# RemoteControl.net
KiCad netlist of a schematic drawn in EAGLE
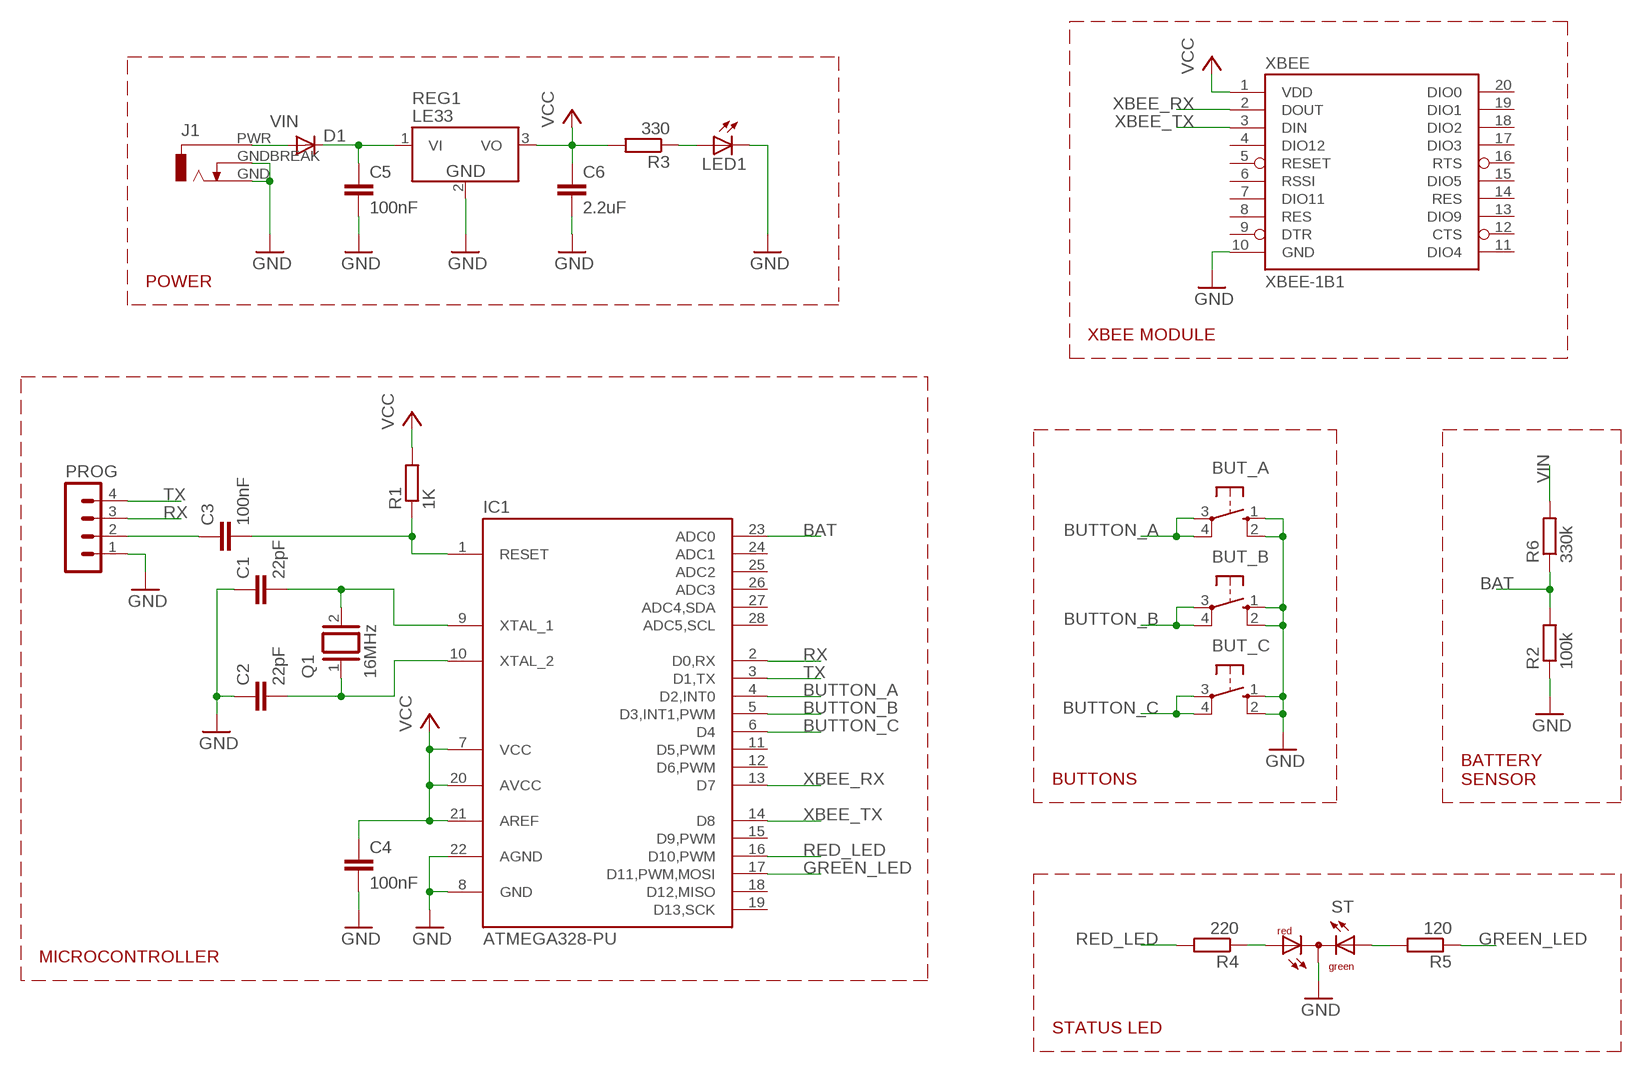
[diagram p0: schematic, sheet 1]

(export (version "E")
  (design (tool "Eeschema 10.0.6"))
  (components
    (comp (ref "BUT_A")
      (value "40-XX")
      (footprint "eagle-import:B3F-40XX")
      (fields (field (name "MF") "OMRON COMPONENTS USA") (field (name "MPN") "B3F-4000"))
      (libsource (lib "eagle-import") (part "40-XX"))
    )
    (comp (ref "BUT_B")
      (value "40-XX")
      (footprint "eagle-import:B3F-40XX")
      (fields (field (name "MF") "OMRON COMPONENTS USA") (field (name "MPN") "B3F-4000"))
      (libsource (lib "eagle-import") (part "40-XX"))
    )
    (comp (ref "BUT_C")
      (value "40-XX")
      (footprint "eagle-import:B3F-40XX")
      (fields (field (name "MF") "OMRON COMPONENTS USA") (field (name "MPN") "B3F-4000"))
      (libsource (lib "eagle-import") (part "40-XX"))
    )
    (comp (ref "C1")
      (value "22pF")
      (footprint "eagle-import:C050-024X044")
      (libsource (lib "eagle-import") (part "C-EU050-024X044"))
    )
    (comp (ref "C2")
      (value "22pF")
      (footprint "eagle-import:C050-024X044")
      (libsource (lib "eagle-import") (part "C-EU050-024X044"))
    )
    (comp (ref "C3")
      (value "100nF")
      (footprint "eagle-import:C050-025X075")
      (libsource (lib "eagle-import") (part "C-EU050-025X075"))
    )
    (comp (ref "C4")
      (value "100nF")
      (footprint "eagle-import:C050-025X075")
      (libsource (lib "eagle-import") (part "C-EU050-025X075"))
    )
    (comp (ref "C5")
      (value "100nF")
      (footprint "eagle-import:C050-025X075")
      (libsource (lib "eagle-import") (part "C-EU050-025X075"))
    )
    (comp (ref "C6")
      (value "2.2uF")
      (footprint "eagle-import:C050-035X075")
      (libsource (lib "eagle-import") (part "C-EU050-035X075"))
    )
    (comp (ref "D1")
      (value "1N4148DO35-7")
      (footprint "eagle-import:DO35-7")
      (libsource (lib "eagle-import") (part "1N4148DO35-7"))
    )
    (comp (ref "IC1")
      (value "ATMEGA328-PU")
      (footprint "eagle-import:DIL28-3")
      (libsource (lib "eagle-import") (part "ATMEGA328-PU"))
    )
    (comp (ref "J1")
      (value "DC_JACKPTH")
      (footprint "eagle-import:POWER_JACK_PTH")
      (libsource (lib "eagle-import") (part "DC_JACKPTH"))
    )
    (comp (ref "LED1")
      (value "LED3MM")
      (footprint "eagle-import:LED3MM")
      (libsource (lib "eagle-import") (part "LED3MM"))
    )
    (comp (ref "PROG")
      (value "MA04-1")
      (footprint "eagle-import:MA04-1")
      (libsource (lib "eagle-import") (part "MA04-1"))
    )
    (comp (ref "Q1")
      (value "16MHz")
      (footprint "eagle-import:QS")
      (libsource (lib "eagle-import") (part "XTAL/S"))
    )
    (comp (ref "R1")
      (value "1K")
      (footprint "eagle-import:0207_7")
      (libsource (lib "eagle-import") (part "R-EU_0207/7"))
    )
    (comp (ref "R2")
      (value "100k")
      (footprint "eagle-import:0207_7")
      (libsource (lib "eagle-import") (part "R-EU_0207/7"))
    )
    (comp (ref "R3")
      (value "330")
      (footprint "eagle-import:0207_7")
      (libsource (lib "eagle-import") (part "R-EU_0207/7"))
    )
    (comp (ref "R4")
      (value "220")
      (footprint "eagle-import:0207_7")
      (libsource (lib "eagle-import") (part "R-EU_0207/7"))
    )
    (comp (ref "R5")
      (value "120")
      (footprint "eagle-import:0207_7")
      (libsource (lib "eagle-import") (part "R-EU_0207/7"))
    )
    (comp (ref "R6")
      (value "330k")
      (footprint "eagle-import:0207_7")
      (libsource (lib "eagle-import") (part "R-EU_0207/7"))
    )
    (comp (ref "REG1")
      (value "LE33")
      (footprint "eagle-import:TO-92")
      (libsource (lib "eagle-import") (part "LE33"))
    )
    (comp (ref "ST")
      (value "DUOLED-RG-C")
      (footprint "eagle-import:DUOLED-C-5MM")
      (libsource (lib "eagle-import") (part "DUOLED-RG-C"))
    )
    (comp (ref "XBEE")
      (value "XBEE-1B1")
      (footprint "eagle-import:XBEE-1")
      (libsource (lib "eagle-import") (part "XBEE-1B1"))
    )
  )
  (nets
    (net (code "1") (name "/BAT") (class "Default")
      (node (ref "IC1") (pin "23") (pinfunction "ADC0_23") (pintype "bidirectional"))
      (node (ref "R2") (pin "2") (pinfunction "2_2") (pintype "passive"))
      (node (ref "R6") (pin "1") (pinfunction "1_1") (pintype "passive"))
    )
    (net (code "2") (name "/BUTTON_A") (class "Default")
      (node (ref "BUT_A") (pin "3") (pinfunction "P_3") (pintype "passive"))
      (node (ref "BUT_A") (pin "4") (pinfunction "P1_4") (pintype "passive"))
      (node (ref "IC1") (pin "4") (pinfunction "D2,INT0_4") (pintype "bidirectional"))
    )
    (net (code "3") (name "/BUTTON_B") (class "Default")
      (node (ref "BUT_B") (pin "3") (pinfunction "P_3") (pintype "passive"))
      (node (ref "BUT_B") (pin "4") (pinfunction "P1_4") (pintype "passive"))
      (node (ref "IC1") (pin "5") (pinfunction "D3,INT1,PWM_5") (pintype "bidirectional"))
    )
    (net (code "4") (name "/BUTTON_C") (class "Default")
      (node (ref "BUT_C") (pin "3") (pinfunction "P_3") (pintype "passive"))
      (node (ref "BUT_C") (pin "4") (pinfunction "P1_4") (pintype "passive"))
      (node (ref "IC1") (pin "6") (pinfunction "D4_6") (pintype "bidirectional"))
    )
    (net (code "5") (name "/GREEN_LED") (class "Default")
      (node (ref "IC1") (pin "17") (pinfunction "D11,PWM,MOSI_17") (pintype "bidirectional"))
      (node (ref "R5") (pin "1") (pinfunction "1_1") (pintype "passive"))
    )
    (net (code "6") (name "/RED_LED") (class "Default")
      (node (ref "IC1") (pin "16") (pinfunction "D10,PWM_16") (pintype "bidirectional"))
      (node (ref "R4") (pin "2") (pinfunction "2_2") (pintype "passive"))
    )
    (net (code "7") (name "/RX") (class "Default")
      (node (ref "IC1") (pin "2") (pinfunction "D0,RX_2") (pintype "bidirectional"))
      (node (ref "PROG") (pin "3") (pinfunction "3_3") (pintype "passive"))
    )
    (net (code "8") (name "/TX") (class "Default")
      (node (ref "IC1") (pin "3") (pinfunction "D1,TX_3") (pintype "bidirectional"))
      (node (ref "PROG") (pin "4") (pinfunction "4_4") (pintype "passive"))
    )
    (net (code "9") (name "/VIN") (class "Default")
      (node (ref "D1") (pin "A") (pinfunction "A_A") (pintype "passive"))
      (node (ref "J1") (pin "PWR") (pinfunction "1_PWR") (pintype "passive"))
      (node (ref "R6") (pin "2") (pinfunction "2_2") (pintype "passive"))
    )
    (net (code "10") (name "/XBEE_RX") (class "Default")
      (node (ref "IC1") (pin "13") (pinfunction "D7_13") (pintype "bidirectional"))
      (node (ref "XBEE") (pin "2") (pinfunction "DOUT_2") (pintype "output"))
    )
    (net (code "11") (name "/XBEE_TX") (class "Default")
      (node (ref "IC1") (pin "14") (pinfunction "D8_14") (pintype "bidirectional"))
      (node (ref "XBEE") (pin "3") (pinfunction "DIN_3") (pintype "input"))
    )
    (net (code "12") (name "GND") (class "Default")
      (node (ref "BUT_A") (pin "1") (pinfunction "S_1") (pintype "passive"))
      (node (ref "BUT_A") (pin "2") (pinfunction "S1_2") (pintype "passive"))
      (node (ref "BUT_B") (pin "1") (pinfunction "S_1") (pintype "passive"))
      (node (ref "BUT_B") (pin "2") (pinfunction "S1_2") (pintype "passive"))
      (node (ref "BUT_C") (pin "1") (pinfunction "S_1") (pintype "passive"))
      (node (ref "BUT_C") (pin "2") (pinfunction "S1_2") (pintype "passive"))
      (node (ref "C1") (pin "1") (pinfunction "1_1") (pintype "passive"))
      (node (ref "C2") (pin "1") (pinfunction "1_1") (pintype "passive"))
      (node (ref "C4") (pin "2") (pinfunction "2_2") (pintype "passive"))
      (node (ref "C5") (pin "2") (pinfunction "2_2") (pintype "passive"))
      (node (ref "C6") (pin "2") (pinfunction "2_2") (pintype "passive"))
      (node (ref "IC1") (pin "22") (pinfunction "AGND_22") (pintype "power_in"))
      (node (ref "IC1") (pin "8") (pinfunction "GND_8") (pintype "power_in"))
      (node (ref "J1") (pin "GND") (pinfunction "3_GND") (pintype "passive"))
      (node (ref "J1") (pin "GNDBREAK") (pinfunction "2_GNDBREAK") (pintype "passive"))
      (node (ref "LED1") (pin "K") (pinfunction "C_K") (pintype "passive"))
      (node (ref "PROG") (pin "1") (pinfunction "1_1") (pintype "passive"))
      (node (ref "R2") (pin "1") (pinfunction "1_1") (pintype "passive"))
      (node (ref "REG1") (pin "2") (pinfunction "GND_2") (pintype "bidirectional"))
      (node (ref "ST") (pin "C") (pinfunction "C_C") (pintype "passive"))
      (node (ref "XBEE") (pin "10") (pinfunction "GND_10") (pintype "power_in"))
    )
    (net (code "13") (name "Net-(C3-Pad1)") (class "Default")
      (node (ref "C3") (pin "1") (pinfunction "1_1") (pintype "passive"))
      (node (ref "PROG") (pin "2") (pinfunction "2_2") (pintype "passive"))
    )
    (net (code "14") (name "Net-(IC1-RESET)") (class "Default")
      (node (ref "C3") (pin "2") (pinfunction "2_2") (pintype "passive"))
      (node (ref "IC1") (pin "1") (pinfunction "RESET_1") (pintype "bidirectional"))
      (node (ref "R1") (pin "1") (pinfunction "1_1") (pintype "passive"))
    )
    (net (code "15") (name "Net-(IC1-XTAL_1)") (class "Default")
      (node (ref "C1") (pin "2") (pinfunction "2_2") (pintype "passive"))
      (node (ref "IC1") (pin "9") (pinfunction "XTAL_1_9") (pintype "bidirectional"))
      (node (ref "Q1") (pin "2") (pinfunction "2_2") (pintype "passive"))
    )
    (net (code "16") (name "Net-(IC1-XTAL_2)") (class "Default")
      (node (ref "C2") (pin "2") (pinfunction "2_2") (pintype "passive"))
      (node (ref "IC1") (pin "10") (pinfunction "XTAL_2_10") (pintype "bidirectional"))
      (node (ref "Q1") (pin "1") (pinfunction "1_1") (pintype "passive"))
    )
    (net (code "17") (name "Net-(LED1-PadA)") (class "Default")
      (node (ref "LED1") (pin "A") (pinfunction "A_A") (pintype "passive"))
      (node (ref "R3") (pin "1") (pinfunction "1_1") (pintype "passive"))
    )
    (net (code "18") (name "Net-(R4-Pad1)") (class "Default")
      (node (ref "R4") (pin "1") (pinfunction "1_1") (pintype "passive"))
      (node (ref "ST") (pin "AR") (pinfunction "AR_AR") (pintype "passive"))
    )
    (net (code "19") (name "Net-(REG1-VI)") (class "Default")
      (node (ref "C5") (pin "1") (pinfunction "1_1") (pintype "passive"))
      (node (ref "D1") (pin "C") (pinfunction "C_C") (pintype "passive"))
      (node (ref "REG1") (pin "1") (pinfunction "VI_1") (pintype "bidirectional"))
    )
    (net (code "20") (name "Net-(ST-AG)") (class "Default")
      (node (ref "R5") (pin "2") (pinfunction "2_2") (pintype "passive"))
      (node (ref "ST") (pin "AX") (pinfunction "AG_AX") (pintype "passive"))
    )
    (net (code "21") (name "VCC") (class "Default")
      (node (ref "C4") (pin "1") (pinfunction "1_1") (pintype "passive"))
      (node (ref "C6") (pin "1") (pinfunction "1_1") (pintype "passive"))
      (node (ref "IC1") (pin "20") (pinfunction "AVCC_20") (pintype "passive"))
      (node (ref "IC1") (pin "21") (pinfunction "AREF_21") (pintype "passive"))
      (node (ref "IC1") (pin "7") (pinfunction "VCC_7") (pintype "power_in"))
      (node (ref "R1") (pin "2") (pinfunction "2_2") (pintype "passive"))
      (node (ref "R3") (pin "2") (pinfunction "2_2") (pintype "passive"))
      (node (ref "REG1") (pin "3") (pinfunction "VO_3") (pintype "bidirectional"))
      (node (ref "XBEE") (pin "1") (pinfunction "VDD_1") (pintype "power_in"))
    )
    (net (code "22") (name "unconnected-(IC1-ADC1-Pad24)") (class "Default")
      (node (ref "IC1") (pin "24") (pinfunction "ADC1_24") (pintype "bidirectional"))
    )
    (net (code "23") (name "unconnected-(IC1-ADC2-Pad25)") (class "Default")
      (node (ref "IC1") (pin "25") (pinfunction "ADC2_25") (pintype "bidirectional"))
    )
    (net (code "24") (name "unconnected-(IC1-ADC3-Pad26)") (class "Default")
      (node (ref "IC1") (pin "26") (pinfunction "ADC3_26") (pintype "bidirectional"))
    )
    (net (code "25") (name "unconnected-(IC1-ADC4,SDA-Pad27)") (class "Default")
      (node (ref "IC1") (pin "27") (pinfunction "ADC4,SDA_27") (pintype "bidirectional"))
    )
    (net (code "26") (name "unconnected-(IC1-ADC5,SCL-Pad28)") (class "Default")
      (node (ref "IC1") (pin "28") (pinfunction "ADC5,SCL_28") (pintype "bidirectional"))
    )
    (net (code "27") (name "unconnected-(IC1-D5,PWM-Pad11)") (class "Default")
      (node (ref "IC1") (pin "11") (pinfunction "D5,PWM_11") (pintype "bidirectional"))
    )
    (net (code "28") (name "unconnected-(IC1-D6,PWM-Pad12)") (class "Default")
      (node (ref "IC1") (pin "12") (pinfunction "D6,PWM_12") (pintype "bidirectional"))
    )
    (net (code "29") (name "unconnected-(IC1-D9,PWM-Pad15)") (class "Default")
      (node (ref "IC1") (pin "15") (pinfunction "D9,PWM_15") (pintype "bidirectional"))
    )
    (net (code "30") (name "unconnected-(IC1-D12,MISO-Pad18)") (class "Default")
      (node (ref "IC1") (pin "18") (pinfunction "D12,MISO_18") (pintype "bidirectional"))
    )
    (net (code "31") (name "unconnected-(IC1-D13,SCK-Pad19)") (class "Default")
      (node (ref "IC1") (pin "19") (pinfunction "D13,SCK_19") (pintype "bidirectional"))
    )
    (net (code "32") (name "unconnected-(XBEE-CTS-Pad12)") (class "Default")
      (node (ref "XBEE") (pin "12") (pinfunction "CTS_12") (pintype "output"))
    )
    (net (code "33") (name "unconnected-(XBEE-DIO0-Pad20)") (class "Default")
      (node (ref "XBEE") (pin "20") (pinfunction "DIO0_20") (pintype "bidirectional"))
    )
    (net (code "34") (name "unconnected-(XBEE-DIO1-Pad19)") (class "Default")
      (node (ref "XBEE") (pin "19") (pinfunction "DIO1_19") (pintype "bidirectional"))
    )
    (net (code "35") (name "unconnected-(XBEE-DIO2-Pad18)") (class "Default")
      (node (ref "XBEE") (pin "18") (pinfunction "DIO2_18") (pintype "bidirectional"))
    )
    (net (code "36") (name "unconnected-(XBEE-DIO3-Pad17)") (class "Default")
      (node (ref "XBEE") (pin "17") (pinfunction "DIO3_17") (pintype "bidirectional"))
    )
    (net (code "37") (name "unconnected-(XBEE-DIO4-Pad11)") (class "Default")
      (node (ref "XBEE") (pin "11") (pinfunction "DIO4_11") (pintype "bidirectional"))
    )
    (net (code "38") (name "unconnected-(XBEE-DIO5-Pad15)") (class "Default")
      (node (ref "XBEE") (pin "15") (pinfunction "DIO5_15") (pintype "bidirectional"))
    )
    (net (code "39") (name "unconnected-(XBEE-DIO9-Pad13)") (class "Default")
      (node (ref "XBEE") (pin "13") (pinfunction "DIO9_13") (pintype "bidirectional"))
    )
    (net (code "40") (name "unconnected-(XBEE-DIO11-Pad7)") (class "Default")
      (node (ref "XBEE") (pin "7") (pinfunction "DIO11_7") (pintype "bidirectional"))
    )
    (net (code "41") (name "unconnected-(XBEE-DIO12-Pad4)") (class "Default")
      (node (ref "XBEE") (pin "4") (pinfunction "DIO12_4") (pintype "bidirectional"))
    )
    (net (code "42") (name "unconnected-(XBEE-DTR-Pad9)") (class "Default")
      (node (ref "XBEE") (pin "9") (pinfunction "DTR_9") (pintype "bidirectional"))
    )
    (net (code "43") (name "unconnected-(XBEE-RES-Pad8)") (class "Default")
      (node (ref "XBEE") (pin "8") (pinfunction "RES_8") (pintype "bidirectional"))
    )
    (net (code "44") (name "unconnected-(XBEE-RES-Pad14)") (class "Default")
      (node (ref "XBEE") (pin "14") (pinfunction "RES_14") (pintype "bidirectional"))
    )
    (net (code "45") (name "unconnected-(XBEE-RESET-Pad5)") (class "Default")
      (node (ref "XBEE") (pin "5") (pinfunction "RESET_5") (pintype "input"))
    )
    (net (code "46") (name "unconnected-(XBEE-RSSI-Pad6)") (class "Default")
      (node (ref "XBEE") (pin "6") (pinfunction "RSSI_6") (pintype "bidirectional"))
    )
    (net (code "47") (name "unconnected-(XBEE-RTS-Pad16)") (class "Default")
      (node (ref "XBEE") (pin "16") (pinfunction "RTS_16") (pintype "input"))
    )
  )
)
